# Top_Level.net
KiCad netlist of a schematic drawn in Altium Designer
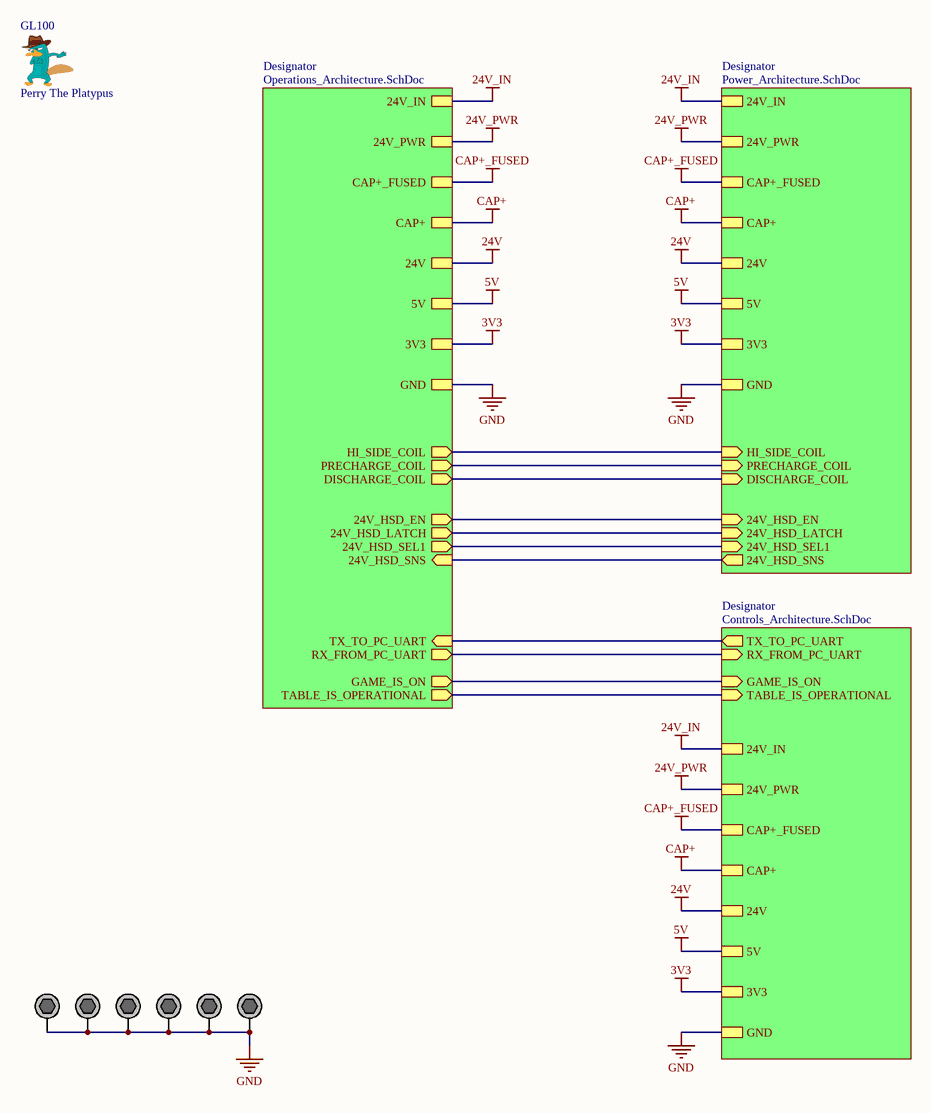
[diagram p0: Top_Level.SchDoc]

(export (version "E")
  (design (tool "Eeschema 10.0.6"))
  (components
    (comp (ref "GL100")
      (value "Perry The Platypus")
      (footprint "Perry the Platypus")
      (libsource (lib "air_hockey_lib") (part "Perry The Platypus"))
    )
    (comp (ref "MH100")
      (value "M3 Mounting Hole Plated")
      (footprint "M3 Screw Hole - Plated")
      (fields (field (name "SOURCE") "UBC Formula Electric.SchLib"))
      (libsource (lib "UBC Formula Electric") (part "Symbol"))
    )
    (comp (ref "MH101")
      (value "M3 Mounting Hole Plated")
      (footprint "M3 Screw Hole - Plated")
      (fields (field (name "SOURCE") "UBC Formula Electric.SchLib"))
      (libsource (lib "UBC Formula Electric") (part "Symbol"))
    )
    (comp (ref "MH102")
      (value "M3 Mounting Hole Plated")
      (footprint "M3 Screw Hole - Plated")
      (fields (field (name "SOURCE") "UBC Formula Electric.SchLib"))
      (libsource (lib "UBC Formula Electric") (part "Symbol"))
    )
    (comp (ref "MH103")
      (value "M3 Mounting Hole Plated")
      (footprint "M3 Screw Hole - Plated")
      (fields (field (name "SOURCE") "UBC Formula Electric.SchLib"))
      (libsource (lib "UBC Formula Electric") (part "Symbol"))
    )
    (comp (ref "MH104")
      (value "M3 Mounting Hole Plated")
      (footprint "M3 Screw Hole - Plated")
      (fields (field (name "SOURCE") "UBC Formula Electric.SchLib"))
      (libsource (lib "UBC Formula Electric") (part "Symbol"))
    )
    (comp (ref "MH105")
      (value "M3 Mounting Hole Plated")
      (footprint "M3 Screw Hole - Plated")
      (fields (field (name "SOURCE") "UBC Formula Electric.SchLib"))
      (libsource (lib "UBC Formula Electric") (part "Symbol"))
    )
  )
  (nets
    (net (code "19") (name "GND") (class "Default")
      (node (ref "MH100") (pin "1") (pinfunction "1_1") (pintype "passive"))
      (node (ref "MH101") (pin "1") (pinfunction "1_1") (pintype "passive"))
      (node (ref "MH102") (pin "1") (pinfunction "1_1") (pintype "passive"))
      (node (ref "MH103") (pin "1") (pinfunction "1_1") (pintype "passive"))
      (node (ref "MH104") (pin "1") (pinfunction "1_1") (pintype "passive"))
      (node (ref "MH105") (pin "1") (pinfunction "1_1") (pintype "passive"))
    )
  )
)
